# io_connectors.net
KiCad netlist of a schematic drawn in Altium Designer
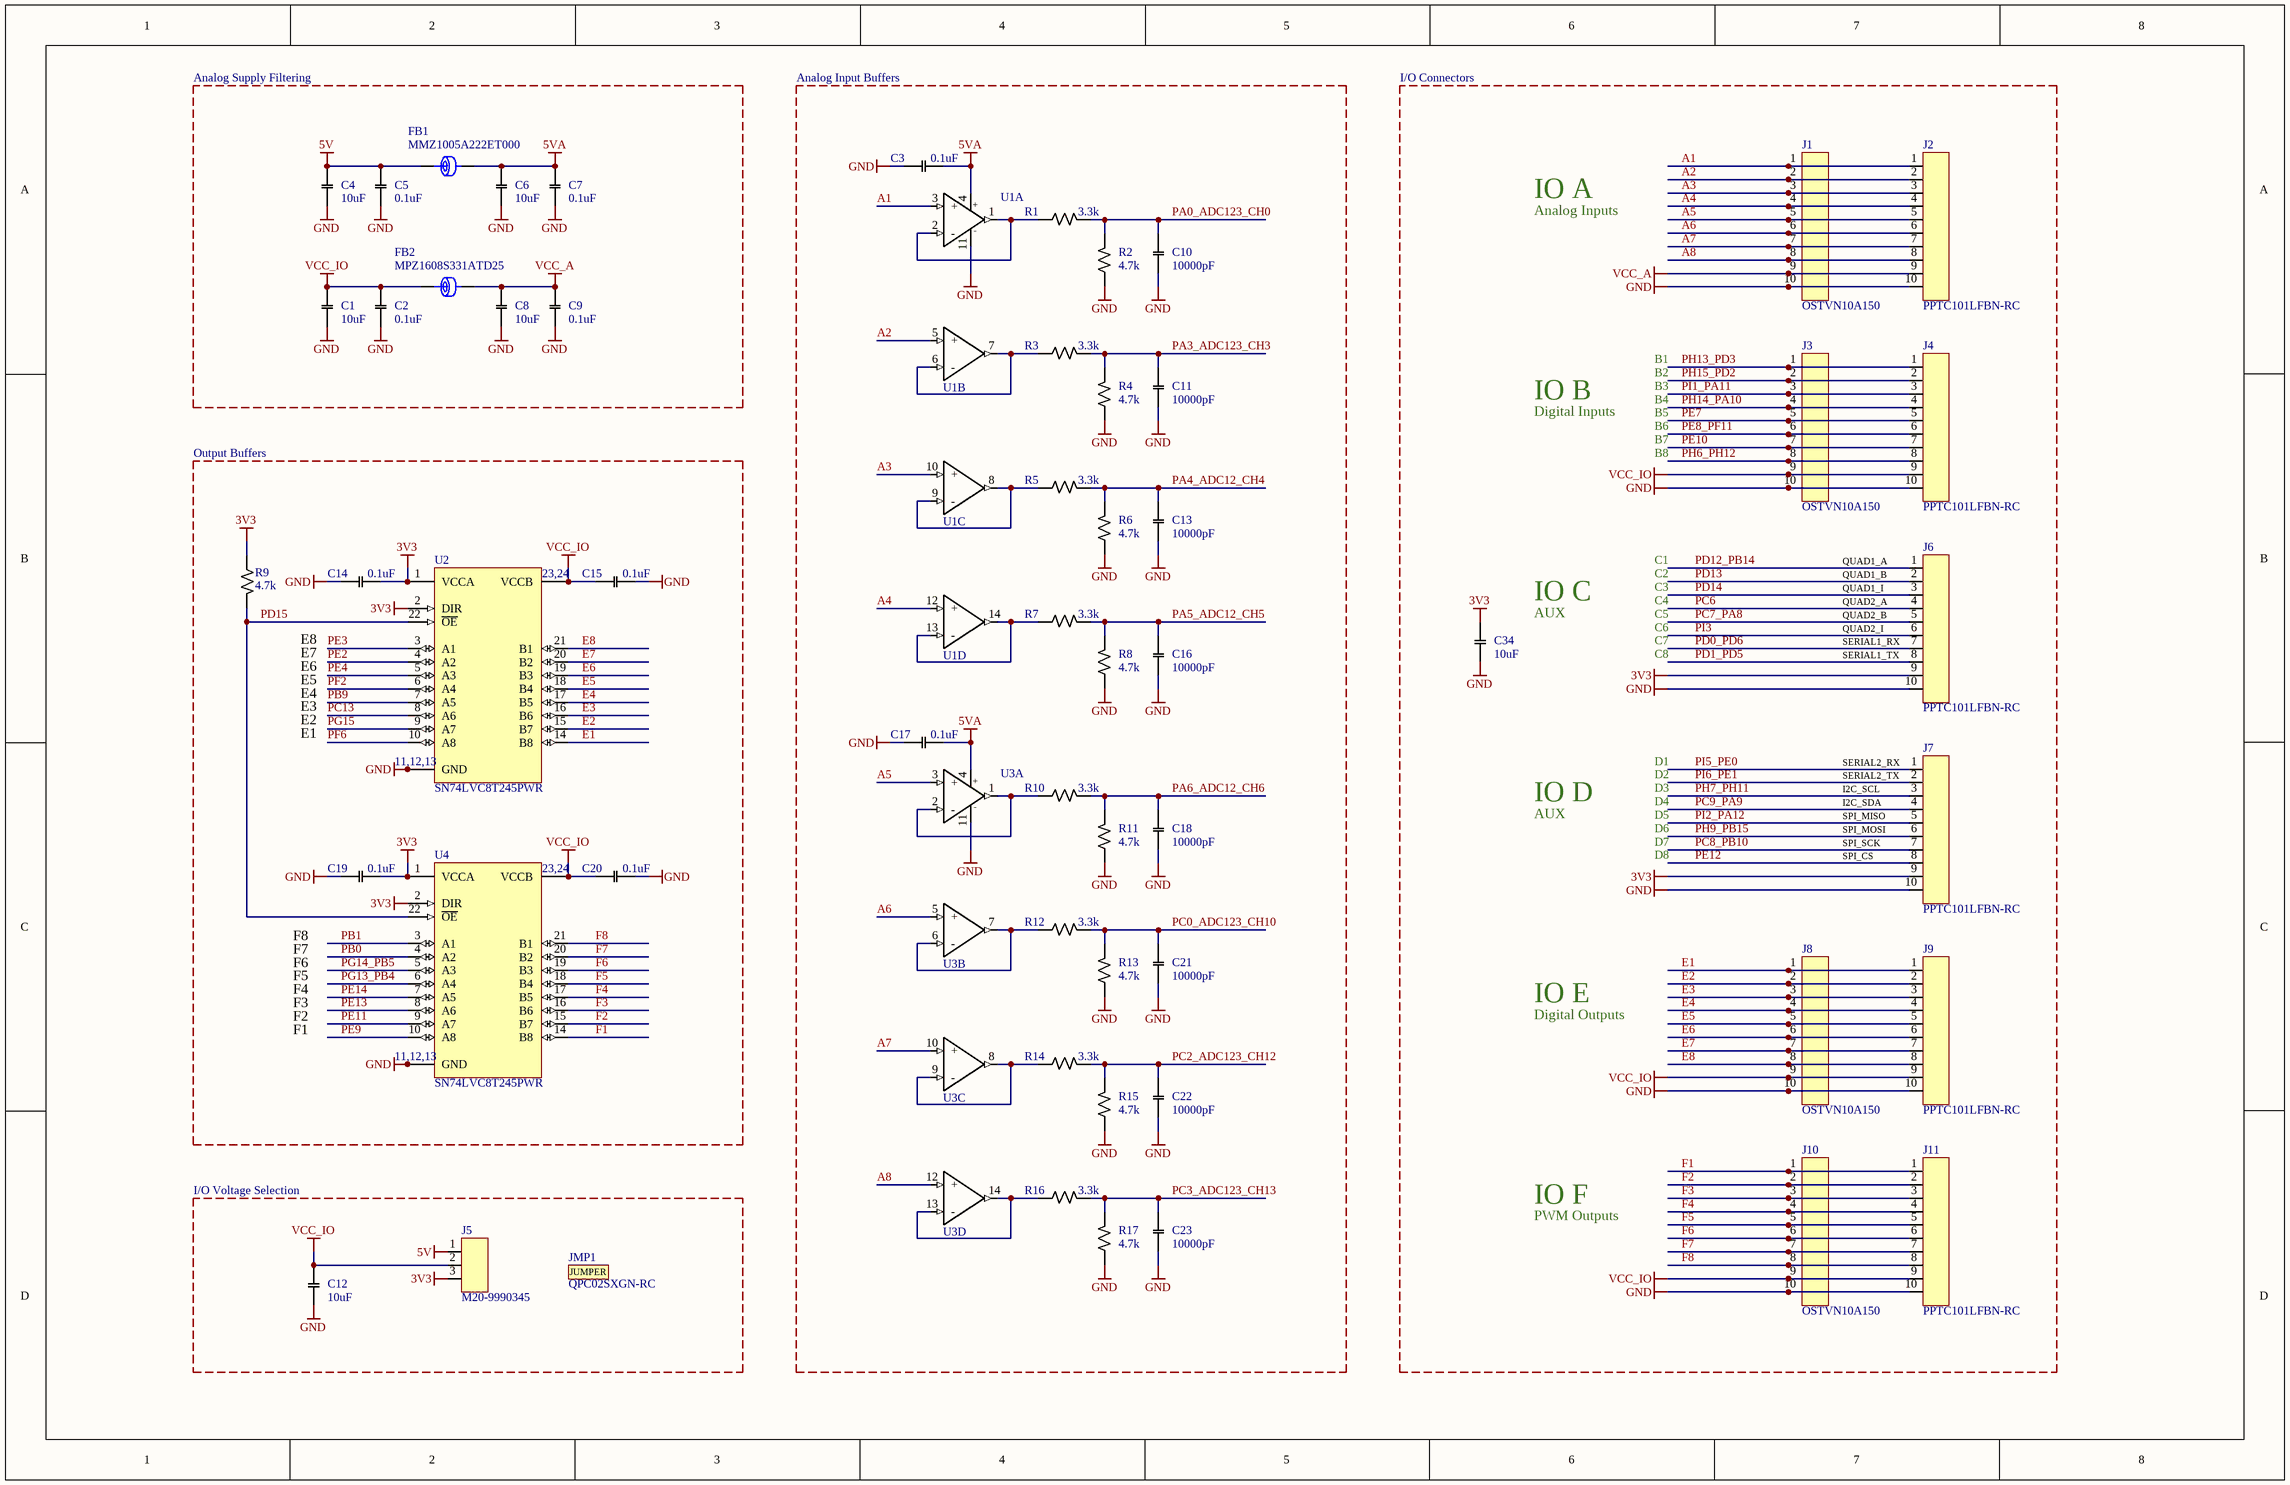
[diagram p0: io_connectors.SchDoc]

(export (version "E")
  (design (tool "Eeschema 10.0.6"))
  (components
    (comp (ref "C1")
      (value "C-10uf-X5R-25V-10%-0805")
      (footprint "C0805")
      (description "Capacitor Ceramic 10uF 25V X5R 10% SMD 0805")
      (fields (field (name "TOLERANCE") "10%") (field (name "CAPACITANCE") "10uF"))
      (libsource (lib "Hebi Robotics") (part "Capacitor"))
    )
    (comp (ref "C2")
      (value "C-0.1uf-X7R-25V-10%-0402")
      (footprint "C0402")
      (description "Capacitor Ceramic 0.1uF 25V X7R 10% SMD 0402")
      (fields (field (name "TOLERANCE") "10%") (field (name "CAPACITANCE") "0.1uF"))
      (libsource (lib "Hebi Robotics") (part "Capacitor"))
    )
    (comp (ref "C3")
      (value "C-0.1uf-X7R-25V-10%-0402")
      (footprint "C0402")
      (description "Capacitor Ceramic 0.1uF 25V X7R 10% SMD 0402")
      (fields (field (name "TOLERANCE") "10%") (field (name "CAPACITANCE") "0.1uF"))
      (libsource (lib "Hebi Robotics") (part "Capacitor"))
    )
    (comp (ref "C4")
      (value "C-10uf-X5R-25V-10%-0805")
      (footprint "C0805")
      (description "Capacitor Ceramic 10uF 25V X5R 10% SMD 0805")
      (fields (field (name "TOLERANCE") "10%") (field (name "CAPACITANCE") "10uF"))
      (libsource (lib "Hebi Robotics") (part "Capacitor"))
    )
    (comp (ref "C5")
      (value "C-0.1uf-X7R-25V-10%-0402")
      (footprint "C0402")
      (description "Capacitor Ceramic 0.1uF 25V X7R 10% SMD 0402")
      (fields (field (name "TOLERANCE") "10%") (field (name "CAPACITANCE") "0.1uF"))
      (libsource (lib "Hebi Robotics") (part "Capacitor"))
    )
    (comp (ref "C6")
      (value "C-10uf-X5R-25V-10%-0805")
      (footprint "C0805")
      (description "Capacitor Ceramic 10uF 25V X5R 10% SMD 0805")
      (fields (field (name "TOLERANCE") "10%") (field (name "CAPACITANCE") "10uF"))
      (libsource (lib "Hebi Robotics") (part "Capacitor"))
    )
    (comp (ref "C7")
      (value "C-0.1uf-X7R-25V-10%-0402")
      (footprint "C0402")
      (description "Capacitor Ceramic 0.1uF 25V X7R 10% SMD 0402")
      (fields (field (name "TOLERANCE") "10%") (field (name "CAPACITANCE") "0.1uF"))
      (libsource (lib "Hebi Robotics") (part "Capacitor"))
    )
    (comp (ref "C8")
      (value "C-10uf-X5R-25V-10%-0805")
      (footprint "C0805")
      (description "Capacitor Ceramic 10uF 25V X5R 10% SMD 0805")
      (fields (field (name "TOLERANCE") "10%") (field (name "CAPACITANCE") "10uF"))
      (libsource (lib "Hebi Robotics") (part "Capacitor"))
    )
    (comp (ref "C9")
      (value "C-0.1uf-X7R-25V-10%-0402")
      (footprint "C0402")
      (description "Capacitor Ceramic 0.1uF 25V X7R 10% SMD 0402")
      (fields (field (name "TOLERANCE") "10%") (field (name "CAPACITANCE") "0.1uF"))
      (libsource (lib "Hebi Robotics") (part "Capacitor"))
    )
    (comp (ref "C10")
      (value "C-10000pf-X7R-50V-10%-0402")
      (footprint "C0402")
      (description "Capacitor Ceramic 10000pF 50V X7R 10% SMD 0402")
      (fields (field (name "TOLERANCE") "10%") (field (name "CAPACITANCE") "10000pF"))
      (libsource (lib "Hebi Robotics") (part "Capacitor"))
    )
    (comp (ref "C11")
      (value "C-10000pf-X7R-50V-10%-0402")
      (footprint "C0402")
      (description "Capacitor Ceramic 10000pF 50V X7R 10% SMD 0402")
      (fields (field (name "TOLERANCE") "10%") (field (name "CAPACITANCE") "10000pF"))
      (libsource (lib "Hebi Robotics") (part "Capacitor"))
    )
    (comp (ref "C12")
      (value "C-10uf-X5R-25V-10%-0805")
      (footprint "C0805")
      (description "Capacitor Ceramic 10uF 25V X5R 10% SMD 0805")
      (fields (field (name "TOLERANCE") "10%") (field (name "CAPACITANCE") "10uF"))
      (libsource (lib "Hebi Robotics") (part "Capacitor"))
    )
    (comp (ref "C13")
      (value "C-10000pf-X7R-50V-10%-0402")
      (footprint "C0402")
      (description "Capacitor Ceramic 10000pF 50V X7R 10% SMD 0402")
      (fields (field (name "TOLERANCE") "10%") (field (name "CAPACITANCE") "10000pF"))
      (libsource (lib "Hebi Robotics") (part "Capacitor"))
    )
    (comp (ref "C14")
      (value "C-0.1uf-X7R-25V-10%-0402")
      (footprint "C0402")
      (description "Capacitor Ceramic 0.1uF 25V X7R 10% SMD 0402")
      (fields (field (name "TOLERANCE") "10%") (field (name "CAPACITANCE") "0.1uF"))
      (libsource (lib "Hebi Robotics") (part "Capacitor"))
    )
    (comp (ref "C15")
      (value "C-0.1uf-X7R-25V-10%-0402")
      (footprint "C0402")
      (description "Capacitor Ceramic 0.1uF 25V X7R 10% SMD 0402")
      (fields (field (name "TOLERANCE") "10%") (field (name "CAPACITANCE") "0.1uF"))
      (libsource (lib "Hebi Robotics") (part "Capacitor"))
    )
    (comp (ref "C16")
      (value "C-10000pf-X7R-50V-10%-0402")
      (footprint "C0402")
      (description "Capacitor Ceramic 10000pF 50V X7R 10% SMD 0402")
      (fields (field (name "TOLERANCE") "10%") (field (name "CAPACITANCE") "10000pF"))
      (libsource (lib "Hebi Robotics") (part "Capacitor"))
    )
    (comp (ref "C17")
      (value "C-0.1uf-X7R-25V-10%-0402")
      (footprint "C0402")
      (description "Capacitor Ceramic 0.1uF 25V X7R 10% SMD 0402")
      (fields (field (name "TOLERANCE") "10%") (field (name "CAPACITANCE") "0.1uF"))
      (libsource (lib "Hebi Robotics") (part "Capacitor"))
    )
    (comp (ref "C18")
      (value "C-10000pf-X7R-50V-10%-0402")
      (footprint "C0402")
      (description "Capacitor Ceramic 10000pF 50V X7R 10% SMD 0402")
      (fields (field (name "TOLERANCE") "10%") (field (name "CAPACITANCE") "10000pF"))
      (libsource (lib "Hebi Robotics") (part "Capacitor"))
    )
    (comp (ref "C19")
      (value "C-0.1uf-X7R-25V-10%-0402")
      (footprint "C0402")
      (description "Capacitor Ceramic 0.1uF 25V X7R 10% SMD 0402")
      (fields (field (name "TOLERANCE") "10%") (field (name "CAPACITANCE") "0.1uF"))
      (libsource (lib "Hebi Robotics") (part "Capacitor"))
    )
    (comp (ref "C20")
      (value "C-0.1uf-X7R-25V-10%-0402")
      (footprint "C0402")
      (description "Capacitor Ceramic 0.1uF 25V X7R 10% SMD 0402")
      (fields (field (name "TOLERANCE") "10%") (field (name "CAPACITANCE") "0.1uF"))
      (libsource (lib "Hebi Robotics") (part "Capacitor"))
    )
    (comp (ref "C21")
      (value "C-10000pf-X7R-50V-10%-0402")
      (footprint "C0402")
      (description "Capacitor Ceramic 10000pF 50V X7R 10% SMD 0402")
      (fields (field (name "TOLERANCE") "10%") (field (name "CAPACITANCE") "10000pF"))
      (libsource (lib "Hebi Robotics") (part "Capacitor"))
    )
    (comp (ref "C22")
      (value "C-10000pf-X7R-50V-10%-0402")
      (footprint "C0402")
      (description "Capacitor Ceramic 10000pF 50V X7R 10% SMD 0402")
      (fields (field (name "TOLERANCE") "10%") (field (name "CAPACITANCE") "10000pF"))
      (libsource (lib "Hebi Robotics") (part "Capacitor"))
    )
    (comp (ref "C23")
      (value "C-10000pf-X7R-50V-10%-0402")
      (footprint "C0402")
      (description "Capacitor Ceramic 10000pF 50V X7R 10% SMD 0402")
      (fields (field (name "TOLERANCE") "10%") (field (name "CAPACITANCE") "10000pF"))
      (libsource (lib "Hebi Robotics") (part "Capacitor"))
    )
    (comp (ref "C34")
      (value "C-10uf-X5R-25V-10%-0805")
      (footprint "C0805")
      (description "Capacitor Ceramic 10uF 25V X5R 10% SMD 0805")
      (fields (field (name "TOLERANCE") "10%") (field (name "CAPACITANCE") "10uF"))
      (libsource (lib "Hebi Robotics") (part "Capacitor"))
    )
    (comp (ref "FB1")
      (value "MMZ1005A222ET000")
      (footprint "FB0402")
      (description "FERRITE BEAD 2.2 KOHM 0402 1LN")
      (libsource (lib "Hebi Robotics") (part "FB"))
    )
    (comp (ref "FB2")
      (value "MPZ1608S331ATD25")
      (footprint "FB0603")
      (description "FERRITE CHIP 330 OHM 1.7A 0603")
      (libsource (lib "Hebi Robotics") (part "FB"))
    )
    (comp (ref "J1")
      (value "OSTVN10A150")
      (footprint "OSTVN10A150")
      (description "CONN TERM BLOCK 2.54MM 10POS PCB")
      (fields (field (name "MANUFACTURER") "On Shore Technology Inc.") (field (name "VOLTAGE") "125V"))
      (libsource (lib "Hebi Robotics") (part "CONN_1_ROW_010_POS"))
    )
    (comp (ref "J2")
      (value "PPTC101LFBN-RC")
      (footprint "PPTC101LFBN-RC")
      (description "CONN HEADER FEMALE 10POS.1\" TIN")
      (fields (field (name "MANUFACTURER") "Sullins Connector Solutions"))
      (libsource (lib "Hebi Robotics") (part "CONN_1_ROW_010_POS"))
    )
    (comp (ref "J3")
      (value "OSTVN10A150")
      (footprint "OSTVN10A150")
      (description "CONN TERM BLOCK 2.54MM 10POS PCB")
      (fields (field (name "MANUFACTURER") "On Shore Technology Inc.") (field (name "VOLTAGE") "125V"))
      (libsource (lib "Hebi Robotics") (part "CONN_1_ROW_010_POS"))
    )
    (comp (ref "J4")
      (value "PPTC101LFBN-RC")
      (footprint "PPTC101LFBN-RC")
      (description "CONN HEADER FEMALE 10POS.1\" TIN")
      (fields (field (name "MANUFACTURER") "Sullins Connector Solutions"))
      (libsource (lib "Hebi Robotics") (part "CONN_1_ROW_010_POS"))
    )
    (comp (ref "J5")
      (value "M20-9990345")
      (footprint "M20-9990345")
      (description "CONN HEADER VERT 3POS 2.54MM")
      (fields (field (name "MANUFACTURER") "Harwin Inc."))
      (libsource (lib "Hebi Robotics") (part "CONN_1_ROW_003_POS"))
    )
    (comp (ref "J6")
      (value "PPTC101LFBN-RC")
      (footprint "PPTC101LFBN-RC")
      (description "CONN HEADER FEMALE 10POS.1\" TIN")
      (fields (field (name "MANUFACTURER") "Sullins Connector Solutions"))
      (libsource (lib "Hebi Robotics") (part "CONN_1_ROW_010_POS"))
    )
    (comp (ref "J7")
      (value "PPTC101LFBN-RC")
      (footprint "PPTC101LFBN-RC")
      (description "CONN HEADER FEMALE 10POS.1\" TIN")
      (fields (field (name "MANUFACTURER") "Sullins Connector Solutions"))
      (libsource (lib "Hebi Robotics") (part "CONN_1_ROW_010_POS"))
    )
    (comp (ref "J8")
      (value "OSTVN10A150")
      (footprint "OSTVN10A150")
      (description "CONN TERM BLOCK 2.54MM 10POS PCB")
      (fields (field (name "MANUFACTURER") "On Shore Technology Inc.") (field (name "VOLTAGE") "125V"))
      (libsource (lib "Hebi Robotics") (part "CONN_1_ROW_010_POS"))
    )
    (comp (ref "J9")
      (value "PPTC101LFBN-RC")
      (footprint "PPTC101LFBN-RC")
      (description "CONN HEADER FEMALE 10POS.1\" TIN")
      (fields (field (name "MANUFACTURER") "Sullins Connector Solutions"))
      (libsource (lib "Hebi Robotics") (part "CONN_1_ROW_010_POS"))
    )
    (comp (ref "J10")
      (value "OSTVN10A150")
      (footprint "OSTVN10A150")
      (description "CONN TERM BLOCK 2.54MM 10POS PCB")
      (fields (field (name "MANUFACTURER") "On Shore Technology Inc.") (field (name "VOLTAGE") "125V"))
      (libsource (lib "Hebi Robotics") (part "CONN_1_ROW_010_POS"))
    )
    (comp (ref "J11")
      (value "PPTC101LFBN-RC")
      (footprint "PPTC101LFBN-RC")
      (description "CONN HEADER FEMALE 10POS.1\" TIN")
      (fields (field (name "MANUFACTURER") "Sullins Connector Solutions"))
      (libsource (lib "Hebi Robotics") (part "CONN_1_ROW_010_POS"))
    )
    (comp (ref "JMP1")
      (value "QPC02SXGN-RC")
      (description "CONN JUMPER SHORTING .100\" GOLD")
      (fields (field (name "MANUFACTURER") "Sullins"))
      (libsource (lib "Hebi Robotics") (part "JUMPER_2"))
    )
    (comp (ref "R1")
      (value "R-3.3k-0.1%-0.063w-0402")
      (footprint "R0402")
      (description "Resistor 0402 3.3k Ohm 0.1% 1-16 Watt")
      (fields (field (name "POWER") "0.063W, 1/16W") (field (name "RESISTANCE") "3.3k"))
      (libsource (lib "Hebi Robotics") (part "Resistor"))
    )
    (comp (ref "R2")
      (value "R-4.7k-0.1%-0.063w-0402")
      (footprint "R0402")
      (description "Resistor 0402 4.7k Ohm 0.1% 1-16 Watt")
      (fields (field (name "POWER") "0.063W, 1/16W") (field (name "RESISTANCE") "4.7k"))
      (libsource (lib "Hebi Robotics") (part "Resistor"))
    )
    (comp (ref "R3")
      (value "R-3.3k-0.1%-0.063w-0402")
      (footprint "R0402")
      (description "Resistor 0402 3.3k Ohm 0.1% 1-16 Watt")
      (fields (field (name "POWER") "0.063W, 1/16W") (field (name "RESISTANCE") "3.3k"))
      (libsource (lib "Hebi Robotics") (part "Resistor"))
    )
    (comp (ref "R4")
      (value "R-4.7k-0.1%-0.063w-0402")
      (footprint "R0402")
      (description "Resistor 0402 4.7k Ohm 0.1% 1-16 Watt")
      (fields (field (name "POWER") "0.063W, 1/16W") (field (name "RESISTANCE") "4.7k"))
      (libsource (lib "Hebi Robotics") (part "Resistor"))
    )
    (comp (ref "R5")
      (value "R-3.3k-0.1%-0.063w-0402")
      (footprint "R0402")
      (description "Resistor 0402 3.3k Ohm 0.1% 1-16 Watt")
      (fields (field (name "POWER") "0.063W, 1/16W") (field (name "RESISTANCE") "3.3k"))
      (libsource (lib "Hebi Robotics") (part "Resistor"))
    )
    (comp (ref "R6")
      (value "R-4.7k-0.1%-0.063w-0402")
      (footprint "R0402")
      (description "Resistor 0402 4.7k Ohm 0.1% 1-16 Watt")
      (fields (field (name "POWER") "0.063W, 1/16W") (field (name "RESISTANCE") "4.7k"))
      (libsource (lib "Hebi Robotics") (part "Resistor"))
    )
    (comp (ref "R7")
      (value "R-3.3k-0.1%-0.063w-0402")
      (footprint "R0402")
      (description "Resistor 0402 3.3k Ohm 0.1% 1-16 Watt")
      (fields (field (name "POWER") "0.063W, 1/16W") (field (name "RESISTANCE") "3.3k"))
      (libsource (lib "Hebi Robotics") (part "Resistor"))
    )
    (comp (ref "R8")
      (value "R-4.7k-0.1%-0.063w-0402")
      (footprint "R0402")
      (description "Resistor 0402 4.7k Ohm 0.1% 1-16 Watt")
      (fields (field (name "POWER") "0.063W, 1/16W") (field (name "RESISTANCE") "4.7k"))
      (libsource (lib "Hebi Robotics") (part "Resistor"))
    )
    (comp (ref "R9")
      (value "R-4.7k-1%-0.063w-0402")
      (footprint "R0402")
      (description "Resistor 0402 4.7k Ohm 1% 1-16 Watt")
      (fields (field (name "POWER") "0.063W, 1/16W") (field (name "RESISTANCE") "4.7k"))
      (libsource (lib "Hebi Robotics") (part "Resistor"))
    )
    (comp (ref "R10")
      (value "R-3.3k-0.1%-0.063w-0402")
      (footprint "R0402")
      (description "Resistor 0402 3.3k Ohm 0.1% 1-16 Watt")
      (fields (field (name "POWER") "0.063W, 1/16W") (field (name "RESISTANCE") "3.3k"))
      (libsource (lib "Hebi Robotics") (part "Resistor"))
    )
    (comp (ref "R11")
      (value "R-4.7k-0.1%-0.063w-0402")
      (footprint "R0402")
      (description "Resistor 0402 4.7k Ohm 0.1% 1-16 Watt")
      (fields (field (name "POWER") "0.063W, 1/16W") (field (name "RESISTANCE") "4.7k"))
      (libsource (lib "Hebi Robotics") (part "Resistor"))
    )
    (comp (ref "R12")
      (value "R-3.3k-0.1%-0.063w-0402")
      (footprint "R0402")
      (description "Resistor 0402 3.3k Ohm 0.1% 1-16 Watt")
      (fields (field (name "POWER") "0.063W, 1/16W") (field (name "RESISTANCE") "3.3k"))
      (libsource (lib "Hebi Robotics") (part "Resistor"))
    )
    (comp (ref "R13")
      (value "R-4.7k-0.1%-0.063w-0402")
      (footprint "R0402")
      (description "Resistor 0402 4.7k Ohm 0.1% 1-16 Watt")
      (fields (field (name "POWER") "0.063W, 1/16W") (field (name "RESISTANCE") "4.7k"))
      (libsource (lib "Hebi Robotics") (part "Resistor"))
    )
    (comp (ref "R14")
      (value "R-3.3k-0.1%-0.063w-0402")
      (footprint "R0402")
      (description "Resistor 0402 3.3k Ohm 0.1% 1-16 Watt")
      (fields (field (name "POWER") "0.063W, 1/16W") (field (name "RESISTANCE") "3.3k"))
      (libsource (lib "Hebi Robotics") (part "Resistor"))
    )
    (comp (ref "R15")
      (value "R-4.7k-0.1%-0.063w-0402")
      (footprint "R0402")
      (description "Resistor 0402 4.7k Ohm 0.1% 1-16 Watt")
      (fields (field (name "POWER") "0.063W, 1/16W") (field (name "RESISTANCE") "4.7k"))
      (libsource (lib "Hebi Robotics") (part "Resistor"))
    )
    (comp (ref "R16")
      (value "R-3.3k-0.1%-0.063w-0402")
      (footprint "R0402")
      (description "Resistor 0402 3.3k Ohm 0.1% 1-16 Watt")
      (fields (field (name "POWER") "0.063W, 1/16W") (field (name "RESISTANCE") "3.3k"))
      (libsource (lib "Hebi Robotics") (part "Resistor"))
    )
    (comp (ref "R17")
      (value "R-4.7k-0.1%-0.063w-0402")
      (footprint "R0402")
      (description "Resistor 0402 4.7k Ohm 0.1% 1-16 Watt")
      (fields (field (name "POWER") "0.063W, 1/16W") (field (name "RESISTANCE") "4.7k"))
      (libsource (lib "Hebi Robotics") (part "Resistor"))
    )
    (comp (ref "U1")
      (value "TSV324IPT")
      (footprint "TSSOP14_ST")
      (description "IC OPAMP GP 1.4MHZ RRO 14TSSOP")
      (fields (field (name "MANUFACTURER") "STMicroelectronics"))
      (libsource (lib "Hebi Robotics") (part "Symbol"))
    )
    (comp (ref "U2")
      (value "SN74LVC8T245PWR")
      (footprint "PW_TSSOP_24_TI")
      (description "IC BUS TRANSCVR 8BIT 24TSSOP")
      (fields (field (name "MANUFACTURER") "Texas Instruments"))
      (libsource (lib "Hebi Robotics") (part "SN74LVC8T245"))
    )
    (comp (ref "U3")
      (value "TSV324IPT")
      (footprint "TSSOP14_ST")
      (description "IC OPAMP GP 1.4MHZ RRO 14TSSOP")
      (fields (field (name "MANUFACTURER") "STMicroelectronics"))
      (libsource (lib "Hebi Robotics") (part "Symbol"))
    )
    (comp (ref "U4")
      (value "SN74LVC8T245PWR")
      (footprint "PW_TSSOP_24_TI")
      (description "IC BUS TRANSCVR 8BIT 24TSSOP")
      (fields (field (name "MANUFACTURER") "Texas Instruments"))
      (libsource (lib "Hebi Robotics") (part "SN74LVC8T245"))
    )
  )
  (nets
    (net (code "1") (name "/A1") (class "Default")
      (node (ref "J1") (pin "1") (pinfunction "1_1") (pintype "passive"))
      (node (ref "J2") (pin "1") (pinfunction "1_1") (pintype "passive"))
      (node (ref "U1") (pin "3") (pinfunction "+_3") (pintype "input"))
    )
    (net (code "2") (name "/A2") (class "Default")
      (node (ref "J1") (pin "2") (pinfunction "2_2") (pintype "passive"))
      (node (ref "J2") (pin "2") (pinfunction "2_2") (pintype "passive"))
      (node (ref "U1") (pin "5") (pinfunction "+_5") (pintype "input"))
    )
    (net (code "3") (name "/A3") (class "Default")
      (node (ref "J1") (pin "3") (pinfunction "3_3") (pintype "passive"))
      (node (ref "J2") (pin "3") (pinfunction "3_3") (pintype "passive"))
      (node (ref "U1") (pin "10") (pinfunction "+_10") (pintype "input"))
    )
    (net (code "4") (name "/A4") (class "Default")
      (node (ref "J1") (pin "4") (pinfunction "4_4") (pintype "passive"))
      (node (ref "J2") (pin "4") (pinfunction "4_4") (pintype "passive"))
      (node (ref "U1") (pin "12") (pinfunction "+_12") (pintype "input"))
    )
    (net (code "5") (name "/A5") (class "Default")
      (node (ref "J1") (pin "5") (pinfunction "5_5") (pintype "passive"))
      (node (ref "J2") (pin "5") (pinfunction "5_5") (pintype "passive"))
      (node (ref "U3") (pin "3") (pinfunction "+_3") (pintype "input"))
    )
    (net (code "6") (name "/A6") (class "Default")
      (node (ref "J1") (pin "6") (pinfunction "6_6") (pintype "passive"))
      (node (ref "J2") (pin "6") (pinfunction "6_6") (pintype "passive"))
      (node (ref "U3") (pin "5") (pinfunction "+_5") (pintype "input"))
    )
    (net (code "7") (name "/A7") (class "Default")
      (node (ref "J1") (pin "7") (pinfunction "7_7") (pintype "passive"))
      (node (ref "J2") (pin "7") (pinfunction "7_7") (pintype "passive"))
      (node (ref "U3") (pin "10") (pinfunction "+_10") (pintype "input"))
    )
    (net (code "8") (name "/A8") (class "Default")
      (node (ref "J1") (pin "8") (pinfunction "8_8") (pintype "passive"))
      (node (ref "J2") (pin "8") (pinfunction "8_8") (pintype "passive"))
      (node (ref "U3") (pin "12") (pinfunction "+_12") (pintype "input"))
    )
    (net (code "9") (name "/E1") (class "Default")
      (node (ref "J8") (pin "1") (pinfunction "1_1") (pintype "passive"))
      (node (ref "J9") (pin "1") (pinfunction "1_1") (pintype "passive"))
      (node (ref "U2") (pin "14") (pinfunction "B8_14") (pintype "bidirectional"))
    )
    (net (code "10") (name "/E2") (class "Default")
      (node (ref "J8") (pin "2") (pinfunction "2_2") (pintype "passive"))
      (node (ref "J9") (pin "2") (pinfunction "2_2") (pintype "passive"))
      (node (ref "U2") (pin "15") (pinfunction "B7_15") (pintype "bidirectional"))
    )
    (net (code "11") (name "/E3") (class "Default")
      (node (ref "J8") (pin "3") (pinfunction "3_3") (pintype "passive"))
      (node (ref "J9") (pin "3") (pinfunction "3_3") (pintype "passive"))
      (node (ref "U2") (pin "16") (pinfunction "B6_16") (pintype "bidirectional"))
    )
    (net (code "12") (name "/E4") (class "Default")
      (node (ref "J8") (pin "4") (pinfunction "4_4") (pintype "passive"))
      (node (ref "J9") (pin "4") (pinfunction "4_4") (pintype "passive"))
      (node (ref "U2") (pin "17") (pinfunction "B5_17") (pintype "bidirectional"))
    )
    (net (code "13") (name "/E5") (class "Default")
      (node (ref "J8") (pin "5") (pinfunction "5_5") (pintype "passive"))
      (node (ref "J9") (pin "5") (pinfunction "5_5") (pintype "passive"))
      (node (ref "U2") (pin "18") (pinfunction "B4_18") (pintype "bidirectional"))
    )
    (net (code "14") (name "/E6") (class "Default")
      (node (ref "J8") (pin "6") (pinfunction "6_6") (pintype "passive"))
      (node (ref "J9") (pin "6") (pinfunction "6_6") (pintype "passive"))
      (node (ref "U2") (pin "19") (pinfunction "B3_19") (pintype "bidirectional"))
    )
    (net (code "15") (name "/E7") (class "Default")
      (node (ref "J8") (pin "7") (pinfunction "7_7") (pintype "passive"))
      (node (ref "J9") (pin "7") (pinfunction "7_7") (pintype "passive"))
      (node (ref "U2") (pin "20") (pinfunction "B2_20") (pintype "bidirectional"))
    )
    (net (code "16") (name "/E8") (class "Default")
      (node (ref "J8") (pin "8") (pinfunction "8_8") (pintype "passive"))
      (node (ref "J9") (pin "8") (pinfunction "8_8") (pintype "passive"))
      (node (ref "U2") (pin "21") (pinfunction "B1_21") (pintype "bidirectional"))
    )
    (net (code "17") (name "/F1") (class "Default")
      (node (ref "J10") (pin "1") (pinfunction "1_1") (pintype "passive"))
      (node (ref "J11") (pin "1") (pinfunction "1_1") (pintype "passive"))
      (node (ref "U4") (pin "14") (pinfunction "B8_14") (pintype "bidirectional"))
    )
    (net (code "18") (name "/F2") (class "Default")
      (node (ref "J10") (pin "2") (pinfunction "2_2") (pintype "passive"))
      (node (ref "J11") (pin "2") (pinfunction "2_2") (pintype "passive"))
      (node (ref "U4") (pin "15") (pinfunction "B7_15") (pintype "bidirectional"))
    )
    (net (code "19") (name "/F3") (class "Default")
      (node (ref "J10") (pin "3") (pinfunction "3_3") (pintype "passive"))
      (node (ref "J11") (pin "3") (pinfunction "3_3") (pintype "passive"))
      (node (ref "U4") (pin "16") (pinfunction "B6_16") (pintype "bidirectional"))
    )
    (net (code "20") (name "/F4") (class "Default")
      (node (ref "J10") (pin "4") (pinfunction "4_4") (pintype "passive"))
      (node (ref "J11") (pin "4") (pinfunction "4_4") (pintype "passive"))
      (node (ref "U4") (pin "17") (pinfunction "B5_17") (pintype "bidirectional"))
    )
    (net (code "21") (name "/F5") (class "Default")
      (node (ref "J10") (pin "5") (pinfunction "5_5") (pintype "passive"))
      (node (ref "J11") (pin "5") (pinfunction "5_5") (pintype "passive"))
      (node (ref "U4") (pin "18") (pinfunction "B4_18") (pintype "bidirectional"))
    )
    (net (code "22") (name "/F6") (class "Default")
      (node (ref "J10") (pin "6") (pinfunction "6_6") (pintype "passive"))
      (node (ref "J11") (pin "6") (pinfunction "6_6") (pintype "passive"))
      (node (ref "U4") (pin "19") (pinfunction "B3_19") (pintype "bidirectional"))
    )
    (net (code "23") (name "/F7") (class "Default")
      (node (ref "J10") (pin "7") (pinfunction "7_7") (pintype "passive"))
      (node (ref "J11") (pin "7") (pinfunction "7_7") (pintype "passive"))
      (node (ref "U4") (pin "20") (pinfunction "B2_20") (pintype "bidirectional"))
    )
    (net (code "24") (name "/F8") (class "Default")
      (node (ref "J10") (pin "8") (pinfunction "8_8") (pintype "passive"))
      (node (ref "J11") (pin "8") (pinfunction "8_8") (pintype "passive"))
      (node (ref "U4") (pin "21") (pinfunction "B1_21") (pintype "bidirectional"))
    )
    (net (code "25") (name "/PA0_ADC123_CH0") (class "Default")
      (node (ref "C10") (pin "2") (pinfunction "2_2") (pintype "passive"))
      (node (ref "R1") (pin "2") (pinfunction "2_2") (pintype "passive"))
      (node (ref "R2") (pin "2") (pinfunction "2_2") (pintype "passive"))
    )
    (net (code "26") (name "/PA3_ADC123_CH3") (class "Default")
      (node (ref "C11") (pin "2") (pinfunction "2_2") (pintype "passive"))
      (node (ref "R3") (pin "2") (pinfunction "2_2") (pintype "passive"))
      (node (ref "R4") (pin "2") (pinfunction "2_2") (pintype "passive"))
    )
    (net (code "27") (name "/PA4_ADC12_CH4") (class "Default")
      (node (ref "C13") (pin "2") (pinfunction "2_2") (pintype "passive"))
      (node (ref "R5") (pin "2") (pinfunction "2_2") (pintype "passive"))
      (node (ref "R6") (pin "2") (pinfunction "2_2") (pintype "passive"))
    )
    (net (code "28") (name "/PA5_ADC12_CH5") (class "Default")
      (node (ref "C16") (pin "2") (pinfunction "2_2") (pintype "passive"))
      (node (ref "R7") (pin "2") (pinfunction "2_2") (pintype "passive"))
      (node (ref "R8") (pin "2") (pinfunction "2_2") (pintype "passive"))
    )
    (net (code "29") (name "/PA6_ADC12_CH6") (class "Default")
      (node (ref "C18") (pin "2") (pinfunction "2_2") (pintype "passive"))
      (node (ref "R10") (pin "2") (pinfunction "2_2") (pintype "passive"))
      (node (ref "R11") (pin "2") (pinfunction "2_2") (pintype "passive"))
    )
    (net (code "30") (name "/PB0") (class "Default")
      (node (ref "U4") (pin "4") (pinfunction "A2_4") (pintype "bidirectional"))
    )
    (net (code "31") (name "/PB1") (class "Default")
      (node (ref "U4") (pin "3") (pinfunction "A1_3") (pintype "bidirectional"))
    )
    (net (code "32") (name "/PB9") (class "Default")
      (node (ref "U2") (pin "7") (pinfunction "A5_7") (pintype "bidirectional"))
    )
    (net (code "33") (name "/PC0_ADC123_CH10") (class "Default")
      (node (ref "C21") (pin "2") (pinfunction "2_2") (pintype "passive"))
      (node (ref "R12") (pin "2") (pinfunction "2_2") (pintype "passive"))
      (node (ref "R13") (pin "2") (pinfunction "2_2") (pintype "passive"))
    )
    (net (code "34") (name "/PC2_ADC123_CH12") (class "Default")
      (node (ref "C22") (pin "2") (pinfunction "2_2") (pintype "passive"))
      (node (ref "R14") (pin "2") (pinfunction "2_2") (pintype "passive"))
      (node (ref "R15") (pin "2") (pinfunction "2_2") (pintype "passive"))
    )
    (net (code "35") (name "/PC3_ADC123_CH13") (class "Default")
      (node (ref "C23") (pin "2") (pinfunction "2_2") (pintype "passive"))
      (node (ref "R16") (pin "2") (pinfunction "2_2") (pintype "passive"))
      (node (ref "R17") (pin "2") (pinfunction "2_2") (pintype "passive"))
    )
    (net (code "36") (name "/PC6") (class "Default")
      (node (ref "J6") (pin "4") (pinfunction "4_4") (pintype "passive"))
    )
    (net (code "37") (name "/PC7_PA8") (class "Default")
      (node (ref "J6") (pin "5") (pinfunction "5_5") (pintype "passive"))
    )
    (net (code "38") (name "/PC8_PB10") (class "Default")
      (node (ref "J7") (pin "7") (pinfunction "7_7") (pintype "passive"))
    )
    (net (code "39") (name "/PC9_PA9") (class "Default")
      (node (ref "J7") (pin "4") (pinfunction "4_4") (pintype "passive"))
    )
    (net (code "40") (name "/PC13") (class "Default")
      (node (ref "U2") (pin "8") (pinfunction "A6_8") (pintype "bidirectional"))
    )
    (net (code "41") (name "/PD0_PD6") (class "Default")
      (node (ref "J6") (pin "7") (pinfunction "7_7") (pintype "passive"))
    )
    (net (code "42") (name "/PD1_PD5") (class "Default")
      (node (ref "J6") (pin "8") (pinfunction "8_8") (pintype "passive"))
    )
    (net (code "43") (name "/PD12_PB14") (class "Default")
      (node (ref "J6") (pin "1") (pinfunction "1_1") (pintype "passive"))
    )
    (net (code "44") (name "/PD13") (class "Default")
      (node (ref "J6") (pin "2") (pinfunction "2_2") (pintype "passive"))
    )
    (net (code "45") (name "/PD14") (class "Default")
      (node (ref "J6") (pin "3") (pinfunction "3_3") (pintype "passive"))
    )
    (net (code "46") (name "/PD15") (class "Default")
      (node (ref "R9") (pin "2") (pinfunction "2_2") (pintype "passive"))
      (node (ref "U2") (pin "22") (pinfunction "OE_22") (pintype "input"))
      (node (ref "U4") (pin "22") (pinfunction "OE_22") (pintype "input"))
    )
    (net (code "47") (name "/PE2") (class "Default")
      (node (ref "U2") (pin "4") (pinfunction "A2_4") (pintype "bidirectional"))
    )
    (net (code "48") (name "/PE3") (class "Default")
      (node (ref "U2") (pin "3") (pinfunction "A1_3") (pintype "bidirectional"))
    )
    (net (code "49") (name "/PE4") (class "Default")
      (node (ref "U2") (pin "5") (pinfunction "A3_5") (pintype "bidirectional"))
    )
    (net (code "50") (name "/PE7") (class "Default")
      (node (ref "J3") (pin "5") (pinfunction "5_5") (pintype "passive"))
      (node (ref "J4") (pin "5") (pinfunction "5_5") (pintype "passive"))
    )
    (net (code "51") (name "/PE8_PF11") (class "Default")
      (node (ref "J3") (pin "6") (pinfunction "6_6") (pintype "passive"))
      (node (ref "J4") (pin "6") (pinfunction "6_6") (pintype "passive"))
    )
    (net (code "52") (name "/PE9") (class "Default")
      (node (ref "U4") (pin "10") (pinfunction "A8_10") (pintype "bidirectional"))
    )
    (net (code "53") (name "/PE10") (class "Default")
      (node (ref "J3") (pin "7") (pinfunction "7_7") (pintype "passive"))
      (node (ref "J4") (pin "7") (pinfunction "7_7") (pintype "passive"))
    )
    (net (code "54") (name "/PE11") (class "Default")
      (node (ref "U4") (pin "9") (pinfunction "A7_9") (pintype "bidirectional"))
    )
    (net (code "55") (name "/PE12") (class "Default")
      (node (ref "J7") (pin "8") (pinfunction "8_8") (pintype "passive"))
    )
    (net (code "56") (name "/PE13") (class "Default")
      (node (ref "U4") (pin "8") (pinfunction "A6_8") (pintype "bidirectional"))
    )
    (net (code "57") (name "/PE14") (class "Default")
      (node (ref "U4") (pin "7") (pinfunction "A5_7") (pintype "bidirectional"))
    )
    (net (code "58") (name "/PF2") (class "Default")
      (node (ref "U2") (pin "6") (pinfunction "A4_6") (pintype "bidirectional"))
    )
    (net (code "59") (name "/PF6") (class "Default")
      (node (ref "U2") (pin "10") (pinfunction "A8_10") (pintype "bidirectional"))
    )
    (net (code "60") (name "/PG13_PB4") (class "Default")
      (node (ref "U4") (pin "6") (pinfunction "A4_6") (pintype "bidirectional"))
    )
    (net (code "61") (name "/PG14_PB5") (class "Default")
      (node (ref "U4") (pin "5") (pinfunction "A3_5") (pintype "bidirectional"))
    )
    (net (code "62") (name "/PG15") (class "Default")
      (node (ref "U2") (pin "9") (pinfunction "A7_9") (pintype "bidirectional"))
    )
    (net (code "63") (name "/PH6_PH12") (class "Default")
      (node (ref "J3") (pin "8") (pinfunction "8_8") (pintype "passive"))
      (node (ref "J4") (pin "8") (pinfunction "8_8") (pintype "passive"))
    )
    (net (code "64") (name "/PH7_PH11") (class "Default")
      (node (ref "J7") (pin "3") (pinfunction "3_3") (pintype "passive"))
    )
    (net (code "65") (name "/PH9_PB15") (class "Default")
      (node (ref "J7") (pin "6") (pinfunction "6_6") (pintype "passive"))
    )
    (net (code "66") (name "/PH13_PD3") (class "Default")
      (node (ref "J3") (pin "1") (pinfunction "1_1") (pintype "passive"))
      (node (ref "J4") (pin "1") (pinfunction "1_1") (pintype "passive"))
    )
    (net (code "67") (name "/PH14_PA10") (class "Default")
      (node (ref "J3") (pin "4") (pinfunction "4_4") (pintype "passive"))
      (node (ref "J4") (pin "4") (pinfunction "4_4") (pintype "passive"))
    )
    (net (code "68") (name "/PH15_PD2") (class "Default")
      (node (ref "J3") (pin "2") (pinfunction "2_2") (pintype "passive"))
      (node (ref "J4") (pin "2") (pinfunction "2_2") (pintype "passive"))
    )
    (net (code "69") (name "/PI1_PA11") (class "Default")
      (node (ref "J3") (pin "3") (pinfunction "3_3") (pintype "passive"))
      (node (ref "J4") (pin "3") (pinfunction "3_3") (pintype "passive"))
    )
    (net (code "70") (name "/PI2_PA12") (class "Default")
      (node (ref "J7") (pin "5") (pinfunction "5_5") (pintype "passive"))
    )
    (net (code "71") (name "/PI3") (class "Default")
      (node (ref "J6") (pin "6") (pinfunction "6_6") (pintype "passive"))
    )
    (net (code "72") (name "/PI5_PE0") (class "Default")
      (node (ref "J7") (pin "1") (pinfunction "1_1") (pintype "passive"))
    )
    (net (code "73") (name "/PI6_PE1") (class "Default")
      (node (ref "J7") (pin "2") (pinfunction "2_2") (pintype "passive"))
    )
    (net (code "74") (name "3V3") (class "Default")
      (node (ref "C14") (pin "2") (pinfunction "2_2") (pintype "passive"))
      (node (ref "C19") (pin "2") (pinfunction "2_2") (pintype "passive"))
      (node (ref "C34") (pin "2") (pinfunction "2_2") (pintype "passive"))
      (node (ref "J5") (pin "3") (pinfunction "3_3") (pintype "passive"))
      (node (ref "J6") (pin "9") (pinfunction "9_9") (pintype "passive"))
      (node (ref "J7") (pin "9") (pinfunction "9_9") (pintype "passive"))
      (node (ref "R9") (pin "1") (pinfunction "1_1") (pintype "passive"))
      (node (ref "U2") (pin "1") (pinfunction "VCCA_1") (pintype "power_in"))
      (node (ref "U2") (pin "2") (pinfunction "DIR_2") (pintype "input"))
      (node (ref "U4") (pin "1") (pinfunction "VCCA_1") (pintype "power_in"))
      (node (ref "U4") (pin "2") (pinfunction "DIR_2") (pintype "input"))
    )
    (net (code "75") (name "5V") (class "Default")
      (node (ref "C4") (pin "2") (pinfunction "2_2") (pintype "passive"))
      (node (ref "C5") (pin "1") (pinfunction "1_1") (pintype "passive"))
      (node (ref "FB1") (pin "1") (pinfunction "1_1") (pintype "passive"))
      (node (ref "J5") (pin "1") (pinfunction "1_1") (pintype "passive"))
    )
    (net (code "76") (name "5VA") (class "Default")
      (node (ref "C17") (pin "1") (pinfunction "1_1") (pintype "passive"))
      (node (ref "C3") (pin "1") (pinfunction "1_1") (pintype "passive"))
      (node (ref "C6") (pin "2") (pinfunction "2_2") (pintype "passive"))
      (node (ref "C7") (pin "1") (pinfunction "1_1") (pintype "passive"))
      (node (ref "FB1") (pin "2") (pinfunction "2_2") (pintype "passive"))
      (node (ref "U1") (pin "4") (pinfunction "V+_4") (pintype "power_in"))
      (node (ref "U3") (pin "4") (pinfunction "V+_4") (pintype "power_in"))
    )
    (net (code "77") (name "GND") (class "Default")
      (node (ref "C1") (pin "1") (pinfunction "1_1") (pintype "passive"))
      (node (ref "C10") (pin "1") (pinfunction "1_1") (pintype "passive"))
      (node (ref "C11") (pin "1") (pinfunction "1_1") (pintype "passive"))
      (node (ref "C12") (pin "1") (pinfunction "1_1") (pintype "passive"))
      (node (ref "C13") (pin "1") (pinfunction "1_1") (pintype "passive"))
      (node (ref "C14") (pin "1") (pinfunction "1_1") (pintype "passive"))
      (node (ref "C15") (pin "1") (pinfunction "1_1") (pintype "passive"))
      (node (ref "C16") (pin "1") (pinfunction "1_1") (pintype "passive"))
      (node (ref "C17") (pin "2") (pinfunction "2_2") (pintype "passive"))
      (node (ref "C18") (pin "1") (pinfunction "1_1") (pintype "passive"))
      (node (ref "C19") (pin "1") (pinfunction "1_1") (pintype "passive"))
      (node (ref "C2") (pin "2") (pinfunction "2_2") (pintype "passive"))
      (node (ref "C20") (pin "1") (pinfunction "1_1") (pintype "passive"))
      (node (ref "C21") (pin "1") (pinfunction "1_1") (pintype "passive"))
      (node (ref "C22") (pin "1") (pinfunction "1_1") (pintype "passive"))
      (node (ref "C23") (pin "1") (pinfunction "1_1") (pintype "passive"))
      (node (ref "C3") (pin "2") (pinfunction "2_2") (pintype "passive"))
      (node (ref "C34") (pin "1") (pinfunction "1_1") (pintype "passive"))
      (node (ref "C4") (pin "1") (pinfunction "1_1") (pintype "passive"))
      (node (ref "C5") (pin "2") (pinfunction "2_2") (pintype "passive"))
      (node (ref "C6") (pin "1") (pinfunction "1_1") (pintype "passive"))
      (node (ref "C7") (pin "2") (pinfunction "2_2") (pintype "passive"))
      (node (ref "C8") (pin "1") (pinfunction "1_1") (pintype "passive"))
      (node (ref "C9") (pin "1") (pinfunction "1_1") (pintype "passive"))
      (node (ref "J1") (pin "10") (pinfunction "10_10") (pintype "passive"))
      (node (ref "J10") (pin "10") (pinfunction "10_10") (pintype "passive"))
      (node (ref "J11") (pin "10") (pinfunction "10_10") (pintype "passive"))
      (node (ref "J2") (pin "10") (pinfunction "10_10") (pintype "passive"))
      (node (ref "J3") (pin "10") (pinfunction "10_10") (pintype "passive"))
      (node (ref "J4") (pin "10") (pinfunction "10_10") (pintype "passive"))
      (node (ref "J6") (pin "10") (pinfunction "10_10") (pintype "passive"))
      (node (ref "J7") (pin "10") (pinfunction "10_10") (pintype "passive"))
      (node (ref "J8") (pin "10") (pinfunction "10_10") (pintype "passive"))
      (node (ref "J9") (pin "10") (pinfunction "10_10") (pintype "passive"))
      (node (ref "R11") (pin "1") (pinfunction "1_1") (pintype "passive"))
      (node (ref "R13") (pin "1") (pinfunction "1_1") (pintype "passive"))
      (node (ref "R15") (pin "1") (pinfunction "1_1") (pintype "passive"))
      (node (ref "R17") (pin "1") (pinfunction "1_1") (pintype "passive"))
      (node (ref "R2") (pin "1") (pinfunction "1_1") (pintype "passive"))
      (node (ref "R4") (pin "1") (pinfunction "1_1") (pintype "passive"))
      (node (ref "R6") (pin "1") (pinfunction "1_1") (pintype "passive"))
      (node (ref "R8") (pin "1") (pinfunction "1_1") (pintype "passive"))
      (node (ref "U1") (pin "11") (pinfunction "V-_11") (pintype "power_in"))
      (node (ref "U2") (pin "11") (pinfunction "GND_11") (pintype "power_in"))
      (node (ref "U2") (pin "12") (pinfunction "GND_12") (pintype "power_in"))
      (node (ref "U2") (pin "13") (pinfunction "GND_13") (pintype "power_in"))
      (node (ref "U3") (pin "11") (pinfunction "V-_11") (pintype "power_in"))
      (node (ref "U4") (pin "11") (pinfunction "GND_11") (pintype "power_in"))
      (node (ref "U4") (pin "12") (pinfunction "GND_12") (pintype "power_in"))
      (node (ref "U4") (pin "13") (pinfunction "GND_13") (pintype "power_in"))
    )
    (net (code "78") (name "Net-(U1A--)") (class "Default")
      (node (ref "R1") (pin "1") (pinfunction "1_1") (pintype "passive"))
      (node (ref "U1") (pin "1") (pinfunction "OUT_1") (pintype "output"))
      (node (ref "U1") (pin "2") (pinfunction "-_2") (pintype "input"))
    )
    (net (code "79") (name "Net-(U1B--)") (class "Default")
      (node (ref "R3") (pin "1") (pinfunction "1_1") (pintype "passive"))
      (node (ref "U1") (pin "6") (pinfunction "-_6") (pintype "input"))
      (node (ref "U1") (pin "7") (pinfunction "OUT_7") (pintype "output"))
    )
    (net (code "80") (name "Net-(U1C--)") (class "Default")
      (node (ref "R5") (pin "1") (pinfunction "1_1") (pintype "passive"))
      (node (ref "U1") (pin "8") (pinfunction "OUT_8") (pintype "output"))
      (node (ref "U1") (pin "9") (pinfunction "-_9") (pintype "input"))
    )
    (net (code "81") (name "Net-(U1D--)") (class "Default")
      (node (ref "R7") (pin "1") (pinfunction "1_1") (pintype "passive"))
      (node (ref "U1") (pin "13") (pinfunction "-_13") (pintype "input"))
      (node (ref "U1") (pin "14") (pinfunction "OUT_14") (pintype "output"))
    )
    (net (code "82") (name "Net-(U3A--)") (class "Default")
      (node (ref "R10") (pin "1") (pinfunction "1_1") (pintype "passive"))
      (node (ref "U3") (pin "1") (pinfunction "OUT_1") (pintype "output"))
      (node (ref "U3") (pin "2") (pinfunction "-_2") (pintype "input"))
    )
    (net (code "83") (name "Net-(U3B--)") (class "Default")
      (node (ref "R12") (pin "1") (pinfunction "1_1") (pintype "passive"))
      (node (ref "U3") (pin "6") (pinfunction "-_6") (pintype "input"))
      (node (ref "U3") (pin "7") (pinfunction "OUT_7") (pintype "output"))
    )
    (net (code "84") (name "Net-(U3C--)") (class "Default")
      (node (ref "R14") (pin "1") (pinfunction "1_1") (pintype "passive"))
      (node (ref "U3") (pin "8") (pinfunction "OUT_8") (pintype "output"))
      (node (ref "U3") (pin "9") (pinfunction "-_9") (pintype "input"))
    )
    (net (code "85") (name "Net-(U3D--)") (class "Default")
      (node (ref "R16") (pin "1") (pinfunction "1_1") (pintype "passive"))
      (node (ref "U3") (pin "13") (pinfunction "-_13") (pintype "input"))
      (node (ref "U3") (pin "14") (pinfunction "OUT_14") (pintype "output"))
    )
    (net (code "86") (name "VCC_A") (class "Default")
      (node (ref "C8") (pin "2") (pinfunction "2_2") (pintype "passive"))
      (node (ref "C9") (pin "2") (pinfunction "2_2") (pintype "passive"))
      (node (ref "FB2") (pin "2") (pinfunction "2_2") (pintype "passive"))
      (node (ref "J1") (pin "9") (pinfunction "9_9") (pintype "passive"))
      (node (ref "J2") (pin "9") (pinfunction "9_9") (pintype "passive"))
    )
    (net (code "87") (name "VCC_IO") (class "Default")
      (node (ref "C1") (pin "2") (pinfunction "2_2") (pintype "passive"))
      (node (ref "C12") (pin "2") (pinfunction "2_2") (pintype "passive"))
      (node (ref "C15") (pin "2") (pinfunction "2_2") (pintype "passive"))
      (node (ref "C2") (pin "1") (pinfunction "1_1") (pintype "passive"))
      (node (ref "C20") (pin "2") (pinfunction "2_2") (pintype "passive"))
      (node (ref "FB2") (pin "1") (pinfunction "1_1") (pintype "passive"))
      (node (ref "J10") (pin "9") (pinfunction "9_9") (pintype "passive"))
      (node (ref "J11") (pin "9") (pinfunction "9_9") (pintype "passive"))
      (node (ref "J3") (pin "9") (pinfunction "9_9") (pintype "passive"))
      (node (ref "J4") (pin "9") (pinfunction "9_9") (pintype "passive"))
      (node (ref "J5") (pin "2") (pinfunction "2_2") (pintype "passive"))
      (node (ref "J8") (pin "9") (pinfunction "9_9") (pintype "passive"))
      (node (ref "J9") (pin "9") (pinfunction "9_9") (pintype "passive"))
      (node (ref "U2") (pin "23") (pinfunction "VCCB_23") (pintype "power_in"))
      (node (ref "U2") (pin "24") (pinfunction "VCCB_24") (pintype "power_in"))
      (node (ref "U4") (pin "23") (pinfunction "VCCB_23") (pintype "power_in"))
      (node (ref "U4") (pin "24") (pinfunction "VCCB_24") (pintype "power_in"))
    )
  )
)
